# lab2_kulikov_buck.net
KiCad netlist of a schematic drawn in Altium Designer
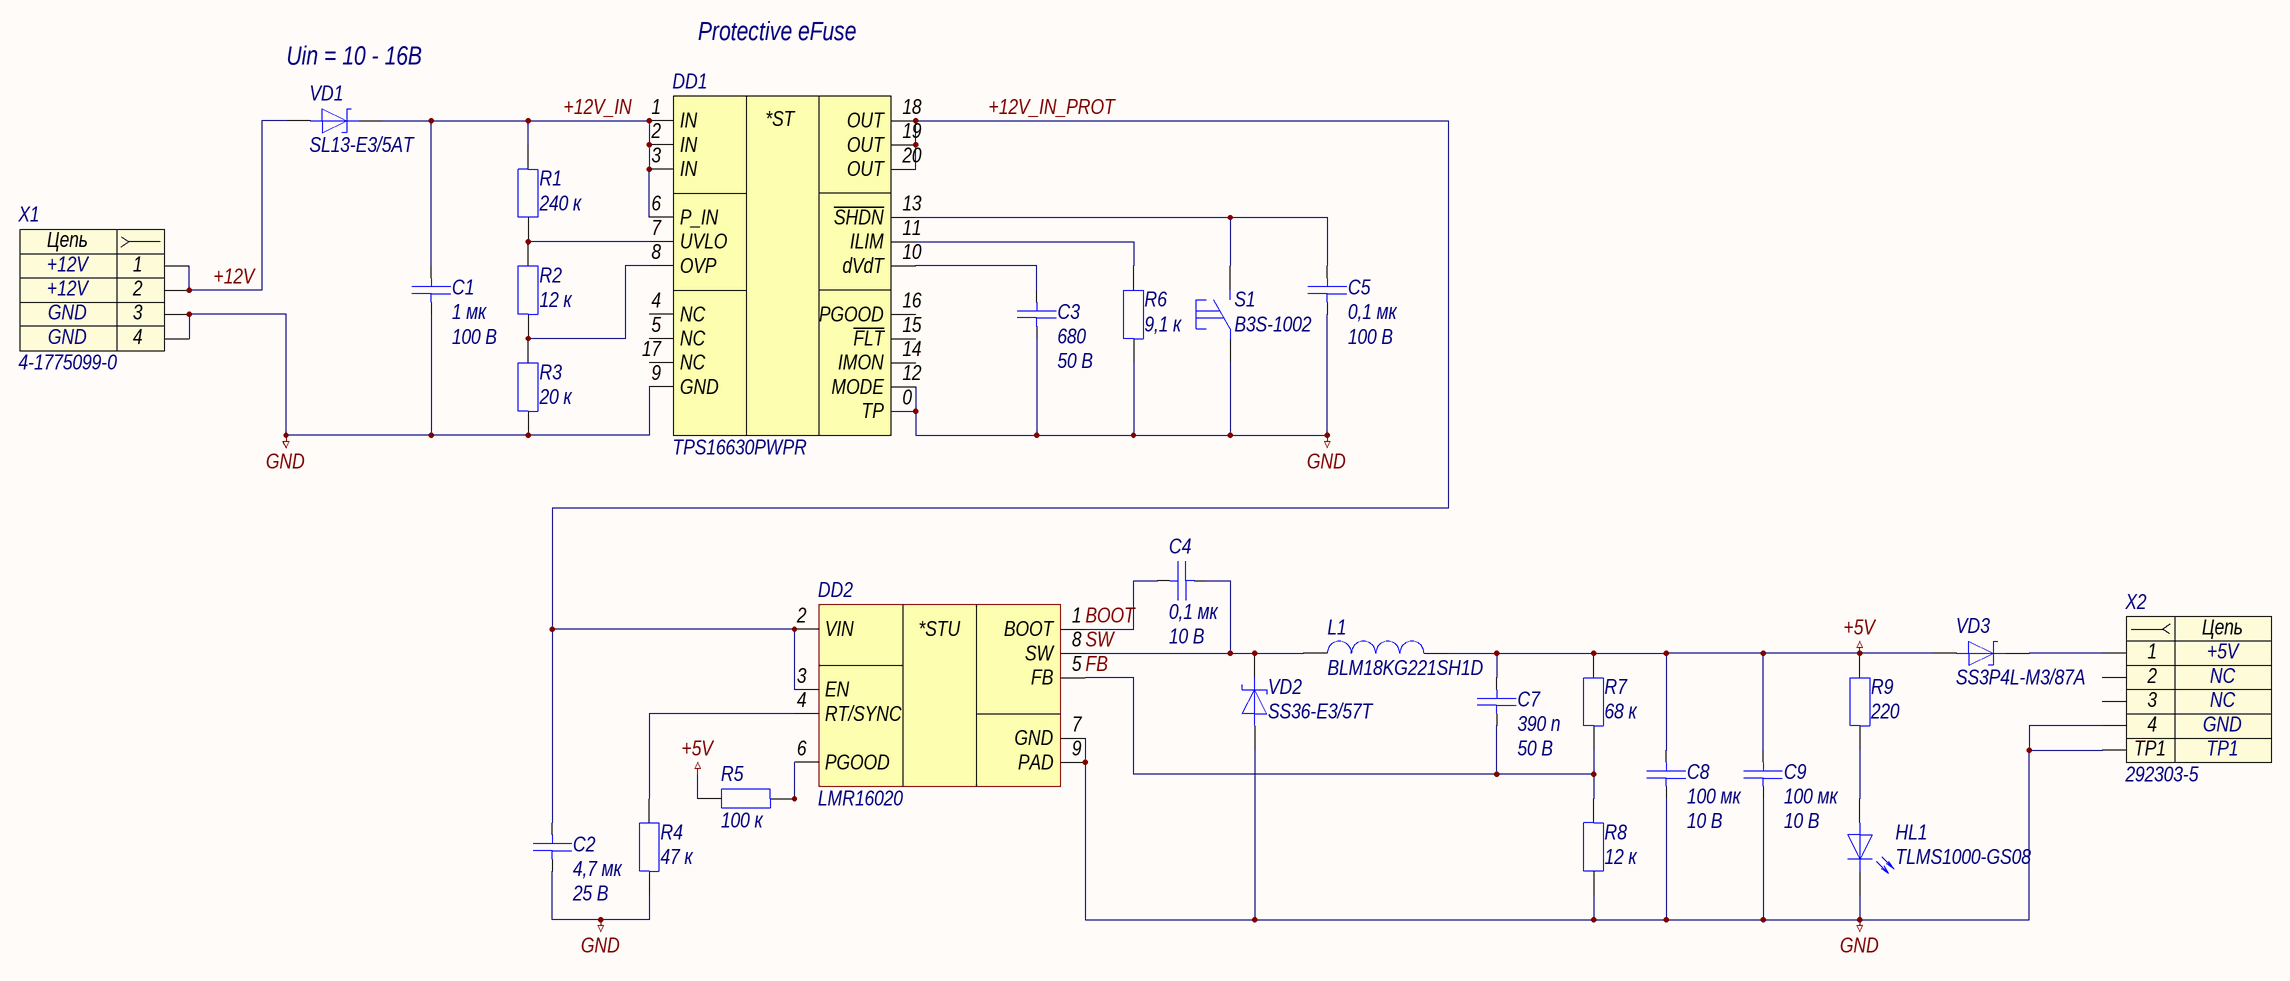
[diagram p0: lab2_kulikov_buck.SchDoc]

(export (version "E")
  (design (tool "Eeschema 10.0.6"))
  (components
    (comp (ref "C1")
      (value "1 мк")
      (footprint "C1206")
      (description "=Описание")
      (fields (field (name "НАПРЯЖЕНИЕ") "100 В"))
      (libsource (lib "Database_Students") (part "CAPACITOR-NONPOLAR"))
    )
    (comp (ref "C2")
      (value "4,7 мк")
      (footprint "C1206")
      (description "=Описание")
      (fields (field (name "НАПРЯЖЕНИЕ") "25 В"))
      (libsource (lib "Database_Students") (part "C-NONPOLAR"))
    )
    (comp (ref "C3")
      (value "680")
      (footprint "C0402")
      (description "=Описание")
      (fields (field (name "НАПРЯЖЕНИЕ") "50 В"))
      (libsource (lib "Database_Students") (part "C-NONPOLAR"))
    )
    (comp (ref "C4")
      (value "0,1 мк")
      (footprint "C0402")
      (description "=Описание")
      (fields (field (name "НАПРЯЖЕНИЕ") "10 В"))
      (libsource (lib "Database_Students") (part "C-NONPOLAR"))
    )
    (comp (ref "C5")
      (value "0,1 мк")
      (footprint "C0603")
      (description "=Описание")
      (fields (field (name "НАПРЯЖЕНИЕ") "100 В"))
      (libsource (lib "Database_Students") (part "C-NONPOLAR"))
    )
    (comp (ref "C7")
      (value "390 п")
      (footprint "C0603")
      (description "=Описание")
      (fields (field (name "НАПРЯЖЕНИЕ") "50 В"))
      (libsource (lib "Database_Students") (part "C-NONPOLAR"))
    )
    (comp (ref "C8")
      (value "100 мк")
      (footprint "C1206")
      (description "=Описание")
      (fields (field (name "НАПРЯЖЕНИЕ") "10 В"))
      (libsource (lib "Database_Students") (part "C-NONPOLAR"))
    )
    (comp (ref "C9")
      (value "100 мк")
      (footprint "C1206")
      (description "=Описание")
      (fields (field (name "НАПРЯЖЕНИЕ") "10 В"))
      (libsource (lib "Database_Students") (part "C-NONPOLAR"))
    )
    (comp (ref "DD1")
      (value "TPS16630PWPR")
      (footprint "HTSSOP-20")
      (description "=Описание")
      (libsource (lib "Database_Students") (part "TPS16630PWPR"))
    )
    (comp (ref "DD2")
      (value "LMR16020")
      (footprint "SOIC127P600X170_HS-9N")
      (libsource (lib "u_lmr16020") (part "Component_1"))
    )
    (comp (ref "HL1")
      (value "TLMS1000-GS08")
      (footprint "HL0603")
      (description "=Описание")
      (libsource (lib "Database_Students") (part "HL-COMMON"))
    )
    (comp (ref "L1")
      (value "BLM18KG221SH1D")
      (footprint "BLM-2-0603")
      (description "=Описание")
      (libsource (lib "Database_Students") (part "FERRITE-BEAD"))
    )
    (comp (ref "R1")
      (value "240 к")
      (footprint "R0603")
      (description "=Описание")
      (libsource (lib "Database_Students") (part "R-COMMON"))
    )
    (comp (ref "R2")
      (value "12 к")
      (footprint "R0603")
      (description "=Описание")
      (libsource (lib "Database_Students") (part "R-COMMON"))
    )
    (comp (ref "R3")
      (value "20 к")
      (footprint "R0603")
      (description "=Описание")
      (libsource (lib "Database_Students") (part "R-COMMON"))
    )
    (comp (ref "R4")
      (value "47 к")
      (footprint "R0603")
      (description "=Описание")
      (libsource (lib "Database_Students") (part "R-COMMON"))
    )
    (comp (ref "R5")
      (value "100 к")
      (footprint "R0603")
      (description "=Описание")
      (libsource (lib "Database_Students") (part "R-COMMON"))
    )
    (comp (ref "R6")
      (value "9,1 к")
      (footprint "R0603")
      (description "=Описание")
      (libsource (lib "Database_Students") (part "R-COMMON"))
    )
    (comp (ref "R7")
      (value "68 к")
      (footprint "R0603")
      (description "=Описание")
      (libsource (lib "Database_Students") (part "R-COMMON"))
    )
    (comp (ref "R8")
      (value "12 к")
      (footprint "R0603")
      (description "=Описание")
      (libsource (lib "Database_Students") (part "R-COMMON"))
    )
    (comp (ref "R9")
      (value "220")
      (footprint "R0603")
      (description "=Описание")
      (libsource (lib "Database_Students") (part "R-COMMON"))
    )
    (comp (ref "S1")
      (value "B3S-1002")
      (footprint "B3S-1002")
      (description "=Описание")
      (libsource (lib "Database_Students") (part "BUTTON"))
    )
    (comp (ref "VD1")
      (value "SL13-E3/5AT")
      (footprint "DO-214AC-510X270X229")
      (description "=Описание")
      (libsource (lib "Database_Students") (part "DIODE-SCHOTTKY"))
    )
    (comp (ref "VD2")
      (value "SS36-E3/57T")
      (footprint "DO-214AB")
      (description "=Описание")
      (libsource (lib "Database_Students") (part "DIODE-SCHOTTKY"))
    )
    (comp (ref "VD3")
      (value "SS3P4L-M3/87A")
      (footprint "TO-277A")
      (description "=Описание")
      (libsource (lib "Database_Students") (part "DIODE-SCHOTTKY"))
    )
    (comp (ref "X1")
      (value "4-1775099-0")
      (footprint "4-1775099-0")
      (description "=Описание")
      (libsource (lib "Database_Students") (part "HEADER-4-SCT"))
    )
    (comp (ref "X2")
      (value "292303-5")
      (footprint "292303-5")
      (description "=Описание")
      (libsource (lib "Database_Students") (part "HEADER-4-TP1-SCT"))
    )
  )
  (nets
    (net (code "1") (name "+5V") (class "Default")
      (node (ref "C7") (pin "1") (pinfunction "1_1") (pintype "passive"))
      (node (ref "C8") (pin "1") (pinfunction "1_1") (pintype "passive"))
      (node (ref "C9") (pin "1") (pinfunction "1_1") (pintype "passive"))
      (node (ref "L1") (pin "2") (pinfunction "2_2") (pintype "passive"))
      (node (ref "R5") (pin "2") (pinfunction "2_2") (pintype "passive"))
      (node (ref "R7") (pin "2") (pinfunction "2_2") (pintype "passive"))
      (node (ref "R9") (pin "2") (pinfunction "2_2") (pintype "passive"))
      (node (ref "VD3") (pin "2") (pinfunction "2_2") (pintype "passive"))
    )
    (net (code "2") (name "/+12V") (class "Default")
      (node (ref "VD1") (pin "2") (pinfunction "2_2") (pintype "passive"))
      (node (ref "X1") (pin "1") (pinfunction "1_1") (pintype "passive"))
      (node (ref "X1") (pin "2") (pinfunction "2_2") (pintype "passive"))
    )
    (net (code "3") (name "/+12V_IN") (class "Default")
      (node (ref "C1") (pin "1") (pinfunction "1_1") (pintype "passive"))
      (node (ref "DD1") (pin "1") (pinfunction "IN_1") (pintype "passive"))
      (node (ref "DD1") (pin "2") (pinfunction "IN_2") (pintype "passive"))
      (node (ref "DD1") (pin "3") (pinfunction "IN_3") (pintype "passive"))
      (node (ref "DD1") (pin "6") (pinfunction "P_IN_6") (pintype "passive"))
      (node (ref "R1") (pin "1") (pinfunction "1_1") (pintype "passive"))
      (node (ref "VD1") (pin "1") (pinfunction "1_1") (pintype "passive"))
    )
    (net (code "4") (name "/+12V_IN_PROT") (class "Default")
      (node (ref "C2") (pin "1") (pinfunction "1_1") (pintype "passive"))
      (node (ref "DD1") (pin "18") (pinfunction "OUT_18") (pintype "passive"))
      (node (ref "DD1") (pin "19") (pinfunction "OUT_19") (pintype "passive"))
      (node (ref "DD1") (pin "20") (pinfunction "OUT_20") (pintype "passive"))
      (node (ref "DD2") (pin "2") (pinfunction "VIN_2") (pintype "passive"))
      (node (ref "DD2") (pin "3") (pinfunction "EN_3") (pintype "passive"))
    )
    (net (code "5") (name "/BOOT") (class "Default")
      (node (ref "C4") (pin "1") (pinfunction "1_1") (pintype "passive"))
      (node (ref "DD2") (pin "1") (pinfunction "BOOT_1") (pintype "passive"))
    )
    (net (code "6") (name "/FB") (class "Default")
      (node (ref "C7") (pin "2") (pinfunction "2_2") (pintype "passive"))
      (node (ref "DD2") (pin "5") (pinfunction "FB_5") (pintype "passive"))
      (node (ref "R7") (pin "1") (pinfunction "1_1") (pintype "passive"))
      (node (ref "R8") (pin "1") (pinfunction "1_1") (pintype "passive"))
    )
    (net (code "7") (name "/SW") (class "Default")
      (node (ref "C4") (pin "2") (pinfunction "2_2") (pintype "passive"))
      (node (ref "DD2") (pin "8") (pinfunction "SW_8") (pintype "passive"))
      (node (ref "L1") (pin "1") (pinfunction "1_1") (pintype "passive"))
      (node (ref "VD2") (pin "1") (pinfunction "1_1") (pintype "passive"))
    )
    (net (code "8") (name "GND") (class "Default")
      (node (ref "C1") (pin "2") (pinfunction "2_2") (pintype "passive"))
      (node (ref "C2") (pin "2") (pinfunction "2_2") (pintype "passive"))
      (node (ref "C3") (pin "2") (pinfunction "2_2") (pintype "passive"))
      (node (ref "C5") (pin "2") (pinfunction "2_2") (pintype "passive"))
      (node (ref "C8") (pin "2") (pinfunction "2_2") (pintype "passive"))
      (node (ref "C9") (pin "2") (pinfunction "2_2") (pintype "passive"))
      (node (ref "DD1") (pin "0") (pinfunction "TP_0") (pintype "passive"))
      (node (ref "DD1") (pin "12") (pinfunction "MODE_12") (pintype "passive"))
      (node (ref "DD1") (pin "9") (pinfunction "GND_9") (pintype "passive"))
      (node (ref "DD2") (pin "7") (pinfunction "GND_7") (pintype "passive"))
      (node (ref "DD2") (pin "9") (pinfunction "PAD_9") (pintype "passive"))
      (node (ref "HL1") (pin "1") (pinfunction "1_1") (pintype "passive"))
      (node (ref "R3") (pin "1") (pinfunction "1_1") (pintype "passive"))
      (node (ref "R4") (pin "1") (pinfunction "1_1") (pintype "passive"))
      (node (ref "R6") (pin "1") (pinfunction "1_1") (pintype "passive"))
      (node (ref "R8") (pin "2") (pinfunction "2_2") (pintype "passive"))
      (node (ref "S1") (pin "1") (pinfunction "1_1") (pintype "passive"))
      (node (ref "VD2") (pin "2") (pinfunction "2_2") (pintype "passive"))
      (node (ref "X1") (pin "3") (pinfunction "3_3") (pintype "passive"))
      (node (ref "X1") (pin "4") (pinfunction "4_4") (pintype "passive"))
      (node (ref "X2") (pin "4") (pinfunction "4_4") (pintype "passive"))
      (node (ref "X2") (pin "TP1") (pinfunction "TP1_TP1") (pintype "passive"))
    )
    (net (code "9") (name "Net-(DD1-ILIM)") (class "Default")
      (node (ref "DD1") (pin "11") (pinfunction "ILIM_11") (pintype "passive"))
      (node (ref "R6") (pin "2") (pinfunction "2_2") (pintype "passive"))
    )
    (net (code "10") (name "Net-(DD1-OVP)") (class "Default")
      (node (ref "DD1") (pin "8") (pinfunction "OVP_8") (pintype "passive"))
      (node (ref "R2") (pin "1") (pinfunction "1_1") (pintype "passive"))
      (node (ref "R3") (pin "2") (pinfunction "2_2") (pintype "passive"))
    )
    (net (code "11") (name "Net-(DD1-UVLO)") (class "Default")
      (node (ref "DD1") (pin "7") (pinfunction "UVLO_7") (pintype "passive"))
      (node (ref "R1") (pin "2") (pinfunction "2_2") (pintype "passive"))
      (node (ref "R2") (pin "2") (pinfunction "2_2") (pintype "passive"))
    )
    (net (code "12") (name "Net-(DD1-dVdT)") (class "Default")
      (node (ref "C3") (pin "1") (pinfunction "1_1") (pintype "passive"))
      (node (ref "DD1") (pin "10") (pinfunction "dVdT_10") (pintype "passive"))
    )
    (net (code "13") (name "Net-(DD1-~{SHDN})") (class "Default")
      (node (ref "C5") (pin "1") (pinfunction "1_1") (pintype "passive"))
      (node (ref "DD1") (pin "13") (pinfunction "~{SHDN}_13") (pintype "passive"))
      (node (ref "S1") (pin "2") (pinfunction "2_2") (pintype "passive"))
    )
    (net (code "14") (name "Net-(DD2-PGOOD)") (class "Default")
      (node (ref "DD2") (pin "6") (pinfunction "PGOOD_6") (pintype "passive"))
      (node (ref "R5") (pin "1") (pinfunction "1_1") (pintype "passive"))
    )
    (net (code "15") (name "Net-(DD2-RT{slash}SYNC)") (class "Default")
      (node (ref "DD2") (pin "4") (pinfunction "RT/SYNC_4") (pintype "passive"))
      (node (ref "R4") (pin "2") (pinfunction "2_2") (pintype "passive"))
    )
    (net (code "16") (name "Net-(HL1-Pad2)") (class "Default")
      (node (ref "HL1") (pin "2") (pinfunction "2_2") (pintype "passive"))
      (node (ref "R9") (pin "1") (pinfunction "1_1") (pintype "passive"))
    )
    (net (code "17") (name "Net-(VD3-Pad1)") (class "Default")
      (node (ref "VD3") (pin "1") (pinfunction "1_1") (pintype "passive"))
      (node (ref "X2") (pin "1") (pinfunction "1_1") (pintype "passive"))
    )
    (net (code "18") (name "unconnected-(DD1-IMON-Pad14)") (class "Default")
      (node (ref "DD1") (pin "14") (pinfunction "IMON_14") (pintype "passive"))
    )
    (net (code "19") (name "unconnected-(DD1-NC-Pad4)") (class "Default")
      (node (ref "DD1") (pin "4") (pinfunction "NC_4") (pintype "passive"))
    )
    (net (code "20") (name "unconnected-(DD1-NC-Pad5)") (class "Default")
      (node (ref "DD1") (pin "5") (pinfunction "NC_5") (pintype "passive"))
    )
    (net (code "21") (name "unconnected-(DD1-NC-Pad17)") (class "Default")
      (node (ref "DD1") (pin "17") (pinfunction "NC_17") (pintype "passive"))
    )
    (net (code "22") (name "unconnected-(DD1-PGOOD-Pad16)") (class "Default")
      (node (ref "DD1") (pin "16") (pinfunction "PGOOD_16") (pintype "passive"))
    )
    (net (code "23") (name "unconnected-(DD1-~{FLT}-Pad15)") (class "Default")
      (node (ref "DD1") (pin "15") (pinfunction "~{FLT}_15") (pintype "passive"))
    )
    (net (code "24") (name "unconnected-(X2-Pad2)") (class "Default")
      (node (ref "X2") (pin "2") (pinfunction "2_2") (pintype "passive"))
    )
    (net (code "25") (name "unconnected-(X2-Pad3)") (class "Default")
      (node (ref "X2") (pin "3") (pinfunction "3_3") (pintype "passive"))
    )
  )
)
